# breakout-40p-v1.net
KiCad netlist of a schematic drawn in EAGLE
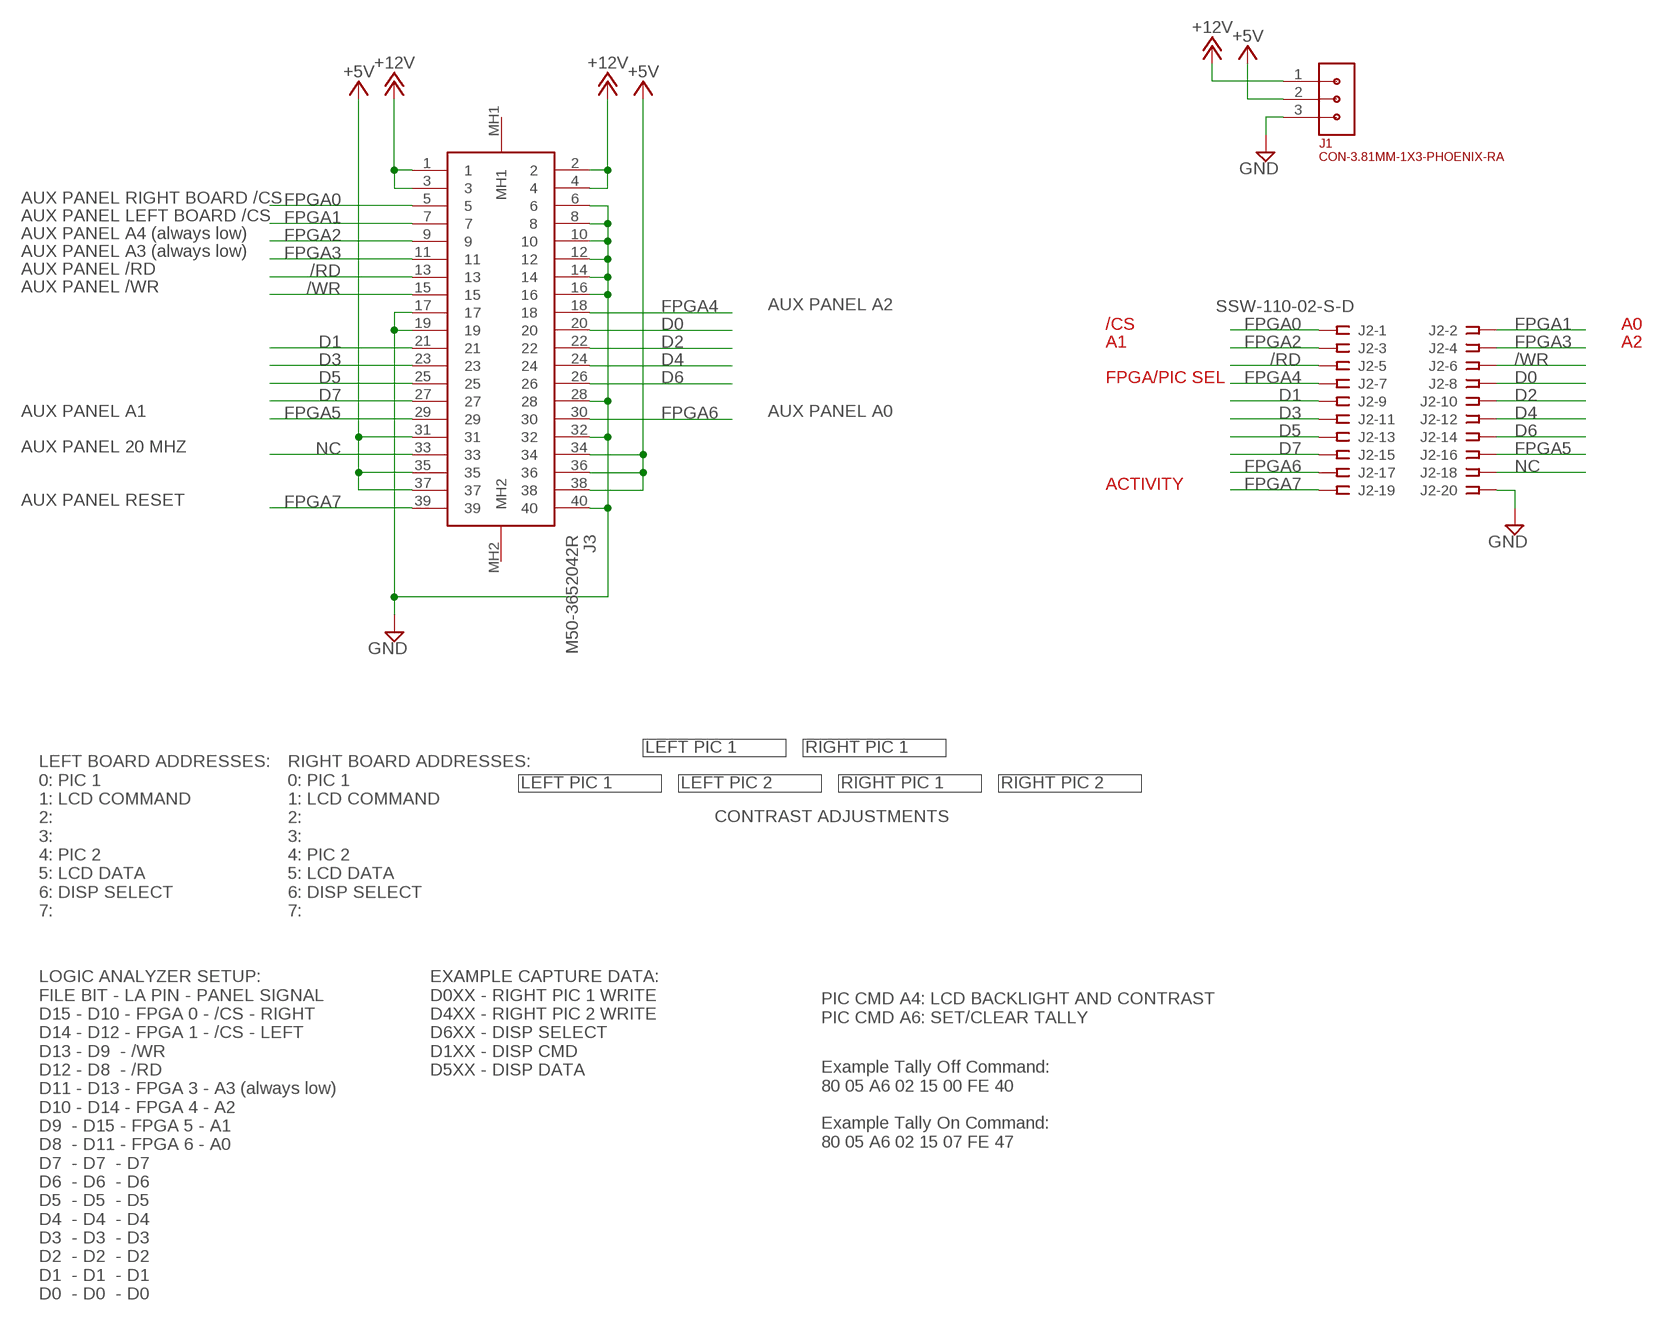
[diagram p0: schematic, sheet 1]

(export (version "E")
  (design (tool "Eeschema 10.0.6"))
  (components
    (comp (ref "J1")
      (value "CON-3.81MM-1X3-PHOENIX-RA")
      (footprint "eagle-import:CON-PHOENIX-3.81-1X3-RA")
      (libsource (lib "eagle-import") (part "CON-3.81MM-1X3-PHOENIX-RA"))
    )
    (comp (ref "J2")
      (value "SSW-110-02-S-D")
      (footprint "eagle-import:SSW-110-02-S-D")
      (libsource (lib "eagle-import") (part "SSW-110-02-S-D"))
    )
    (comp (ref "J3")
      (value "M50-3652042R")
      (footprint "eagle-import:M503652042R")
      (fields (field (name "MOUSER_PART_NUMBER") "855-M50-3652042R"))
      (libsource (lib "eagle-import") (part "M50-3652042R"))
    )
  )
  (nets
    (net (code "1") (name "+5V") (class "Default")
      (node (ref "J1") (pin "2") (pinfunction "2_2") (pintype "bidirectional"))
      (node (ref "J3") (pin "31") (pinfunction "31_31") (pintype "bidirectional"))
      (node (ref "J3") (pin "34") (pinfunction "34_34") (pintype "bidirectional"))
      (node (ref "J3") (pin "35") (pinfunction "35_35") (pintype "bidirectional"))
      (node (ref "J3") (pin "36") (pinfunction "36_36") (pintype "bidirectional"))
      (node (ref "J3") (pin "37") (pinfunction "37_37") (pintype "bidirectional"))
      (node (ref "J3") (pin "38") (pinfunction "38_38") (pintype "bidirectional"))
    )
    (net (code "2") (name "+12V") (class "Default")
      (node (ref "J1") (pin "1") (pinfunction "1_1") (pintype "bidirectional"))
      (node (ref "J3") (pin "1") (pinfunction "1_1") (pintype "bidirectional"))
      (node (ref "J3") (pin "2") (pinfunction "2_2") (pintype "bidirectional"))
      (node (ref "J3") (pin "3") (pinfunction "3_3") (pintype "bidirectional"))
      (node (ref "J3") (pin "4") (pinfunction "4_4") (pintype "bidirectional"))
    )
    (net (code "3") (name "/D0") (class "Default")
      (node (ref "J2") (pin "8") (pinfunction "1_8") (pintype "passive"))
      (node (ref "J3") (pin "20") (pinfunction "20_20") (pintype "bidirectional"))
    )
    (net (code "4") (name "/D1") (class "Default")
      (node (ref "J2") (pin "9") (pinfunction "1_9") (pintype "passive"))
      (node (ref "J3") (pin "21") (pinfunction "21_21") (pintype "bidirectional"))
    )
    (net (code "5") (name "/D2") (class "Default")
      (node (ref "J2") (pin "10") (pinfunction "1_10") (pintype "passive"))
      (node (ref "J3") (pin "22") (pinfunction "22_22") (pintype "bidirectional"))
    )
    (net (code "6") (name "/D3") (class "Default")
      (node (ref "J2") (pin "11") (pinfunction "1_11") (pintype "passive"))
      (node (ref "J3") (pin "23") (pinfunction "23_23") (pintype "bidirectional"))
    )
    (net (code "7") (name "/D4") (class "Default")
      (node (ref "J2") (pin "12") (pinfunction "1_12") (pintype "passive"))
      (node (ref "J3") (pin "24") (pinfunction "24_24") (pintype "bidirectional"))
    )
    (net (code "8") (name "/D5") (class "Default")
      (node (ref "J2") (pin "13") (pinfunction "1_13") (pintype "passive"))
      (node (ref "J3") (pin "25") (pinfunction "25_25") (pintype "bidirectional"))
    )
    (net (code "9") (name "/D6") (class "Default")
      (node (ref "J2") (pin "14") (pinfunction "1_14") (pintype "passive"))
      (node (ref "J3") (pin "26") (pinfunction "26_26") (pintype "bidirectional"))
    )
    (net (code "10") (name "/D7") (class "Default")
      (node (ref "J2") (pin "15") (pinfunction "1_15") (pintype "passive"))
      (node (ref "J3") (pin "27") (pinfunction "27_27") (pintype "bidirectional"))
    )
    (net (code "11") (name "/FPGA0") (class "Default")
      (node (ref "J2") (pin "1") (pinfunction "1_1") (pintype "passive"))
      (node (ref "J3") (pin "5") (pinfunction "5_5") (pintype "bidirectional"))
    )
    (net (code "12") (name "/FPGA1") (class "Default")
      (node (ref "J2") (pin "2") (pinfunction "1_2") (pintype "passive"))
      (node (ref "J3") (pin "7") (pinfunction "7_7") (pintype "bidirectional"))
    )
    (net (code "13") (name "/FPGA2") (class "Default")
      (node (ref "J2") (pin "3") (pinfunction "1_3") (pintype "passive"))
      (node (ref "J3") (pin "9") (pinfunction "9_9") (pintype "bidirectional"))
    )
    (net (code "14") (name "/FPGA3") (class "Default")
      (node (ref "J2") (pin "4") (pinfunction "1_4") (pintype "passive"))
      (node (ref "J3") (pin "11") (pinfunction "11_11") (pintype "bidirectional"))
    )
    (net (code "15") (name "/FPGA4") (class "Default")
      (node (ref "J2") (pin "7") (pinfunction "1_7") (pintype "passive"))
      (node (ref "J3") (pin "18") (pinfunction "18_18") (pintype "bidirectional"))
    )
    (net (code "16") (name "/FPGA5") (class "Default")
      (node (ref "J2") (pin "16") (pinfunction "1_16") (pintype "passive"))
      (node (ref "J3") (pin "29") (pinfunction "29_29") (pintype "bidirectional"))
    )
    (net (code "17") (name "/FPGA6") (class "Default")
      (node (ref "J2") (pin "17") (pinfunction "1_17") (pintype "passive"))
      (node (ref "J3") (pin "30") (pinfunction "30_30") (pintype "bidirectional"))
    )
    (net (code "18") (name "/FPGA7") (class "Default")
      (node (ref "J2") (pin "19") (pinfunction "1_19") (pintype "passive"))
      (node (ref "J3") (pin "39") (pinfunction "39_39") (pintype "bidirectional"))
    )
    (net (code "19") (name "/NC") (class "Default")
      (node (ref "J2") (pin "18") (pinfunction "1_18") (pintype "passive"))
      (node (ref "J3") (pin "33") (pinfunction "33_33") (pintype "bidirectional"))
    )
    (net (code "20") (name "/{slash}RD") (class "Default")
      (node (ref "J2") (pin "5") (pinfunction "1_5") (pintype "passive"))
      (node (ref "J3") (pin "13") (pinfunction "13_13") (pintype "bidirectional"))
    )
    (net (code "21") (name "/{slash}WR") (class "Default")
      (node (ref "J2") (pin "6") (pinfunction "1_6") (pintype "passive"))
      (node (ref "J3") (pin "15") (pinfunction "15_15") (pintype "bidirectional"))
    )
    (net (code "22") (name "GND") (class "Default")
      (node (ref "J1") (pin "3") (pinfunction "3_3") (pintype "bidirectional"))
      (node (ref "J2") (pin "20") (pinfunction "1_20") (pintype "passive"))
      (node (ref "J3") (pin "10") (pinfunction "10_10") (pintype "bidirectional"))
      (node (ref "J3") (pin "12") (pinfunction "12_12") (pintype "bidirectional"))
      (node (ref "J3") (pin "14") (pinfunction "14_14") (pintype "bidirectional"))
      (node (ref "J3") (pin "16") (pinfunction "16_16") (pintype "bidirectional"))
      (node (ref "J3") (pin "17") (pinfunction "17_17") (pintype "bidirectional"))
      (node (ref "J3") (pin "19") (pinfunction "19_19") (pintype "bidirectional"))
      (node (ref "J3") (pin "28") (pinfunction "28_28") (pintype "bidirectional"))
      (node (ref "J3") (pin "32") (pinfunction "32_32") (pintype "bidirectional"))
      (node (ref "J3") (pin "40") (pinfunction "40_40") (pintype "bidirectional"))
      (node (ref "J3") (pin "6") (pinfunction "6_6") (pintype "bidirectional"))
      (node (ref "J3") (pin "8") (pinfunction "8_8") (pintype "bidirectional"))
    )
    (net (code "23") (name "unconnected-(J3-PadMH1)") (class "Default")
      (node (ref "J3") (pin "MH1") (pinfunction "MH1_MH1") (pintype "bidirectional"))
    )
    (net (code "24") (name "unconnected-(J3-PadMH2)") (class "Default")
      (node (ref "J3") (pin "MH2") (pinfunction "MH2_MH2") (pintype "bidirectional"))
    )
  )
)
